# Main_Board.net
KiCad netlist of a schematic drawn in Altium Designer
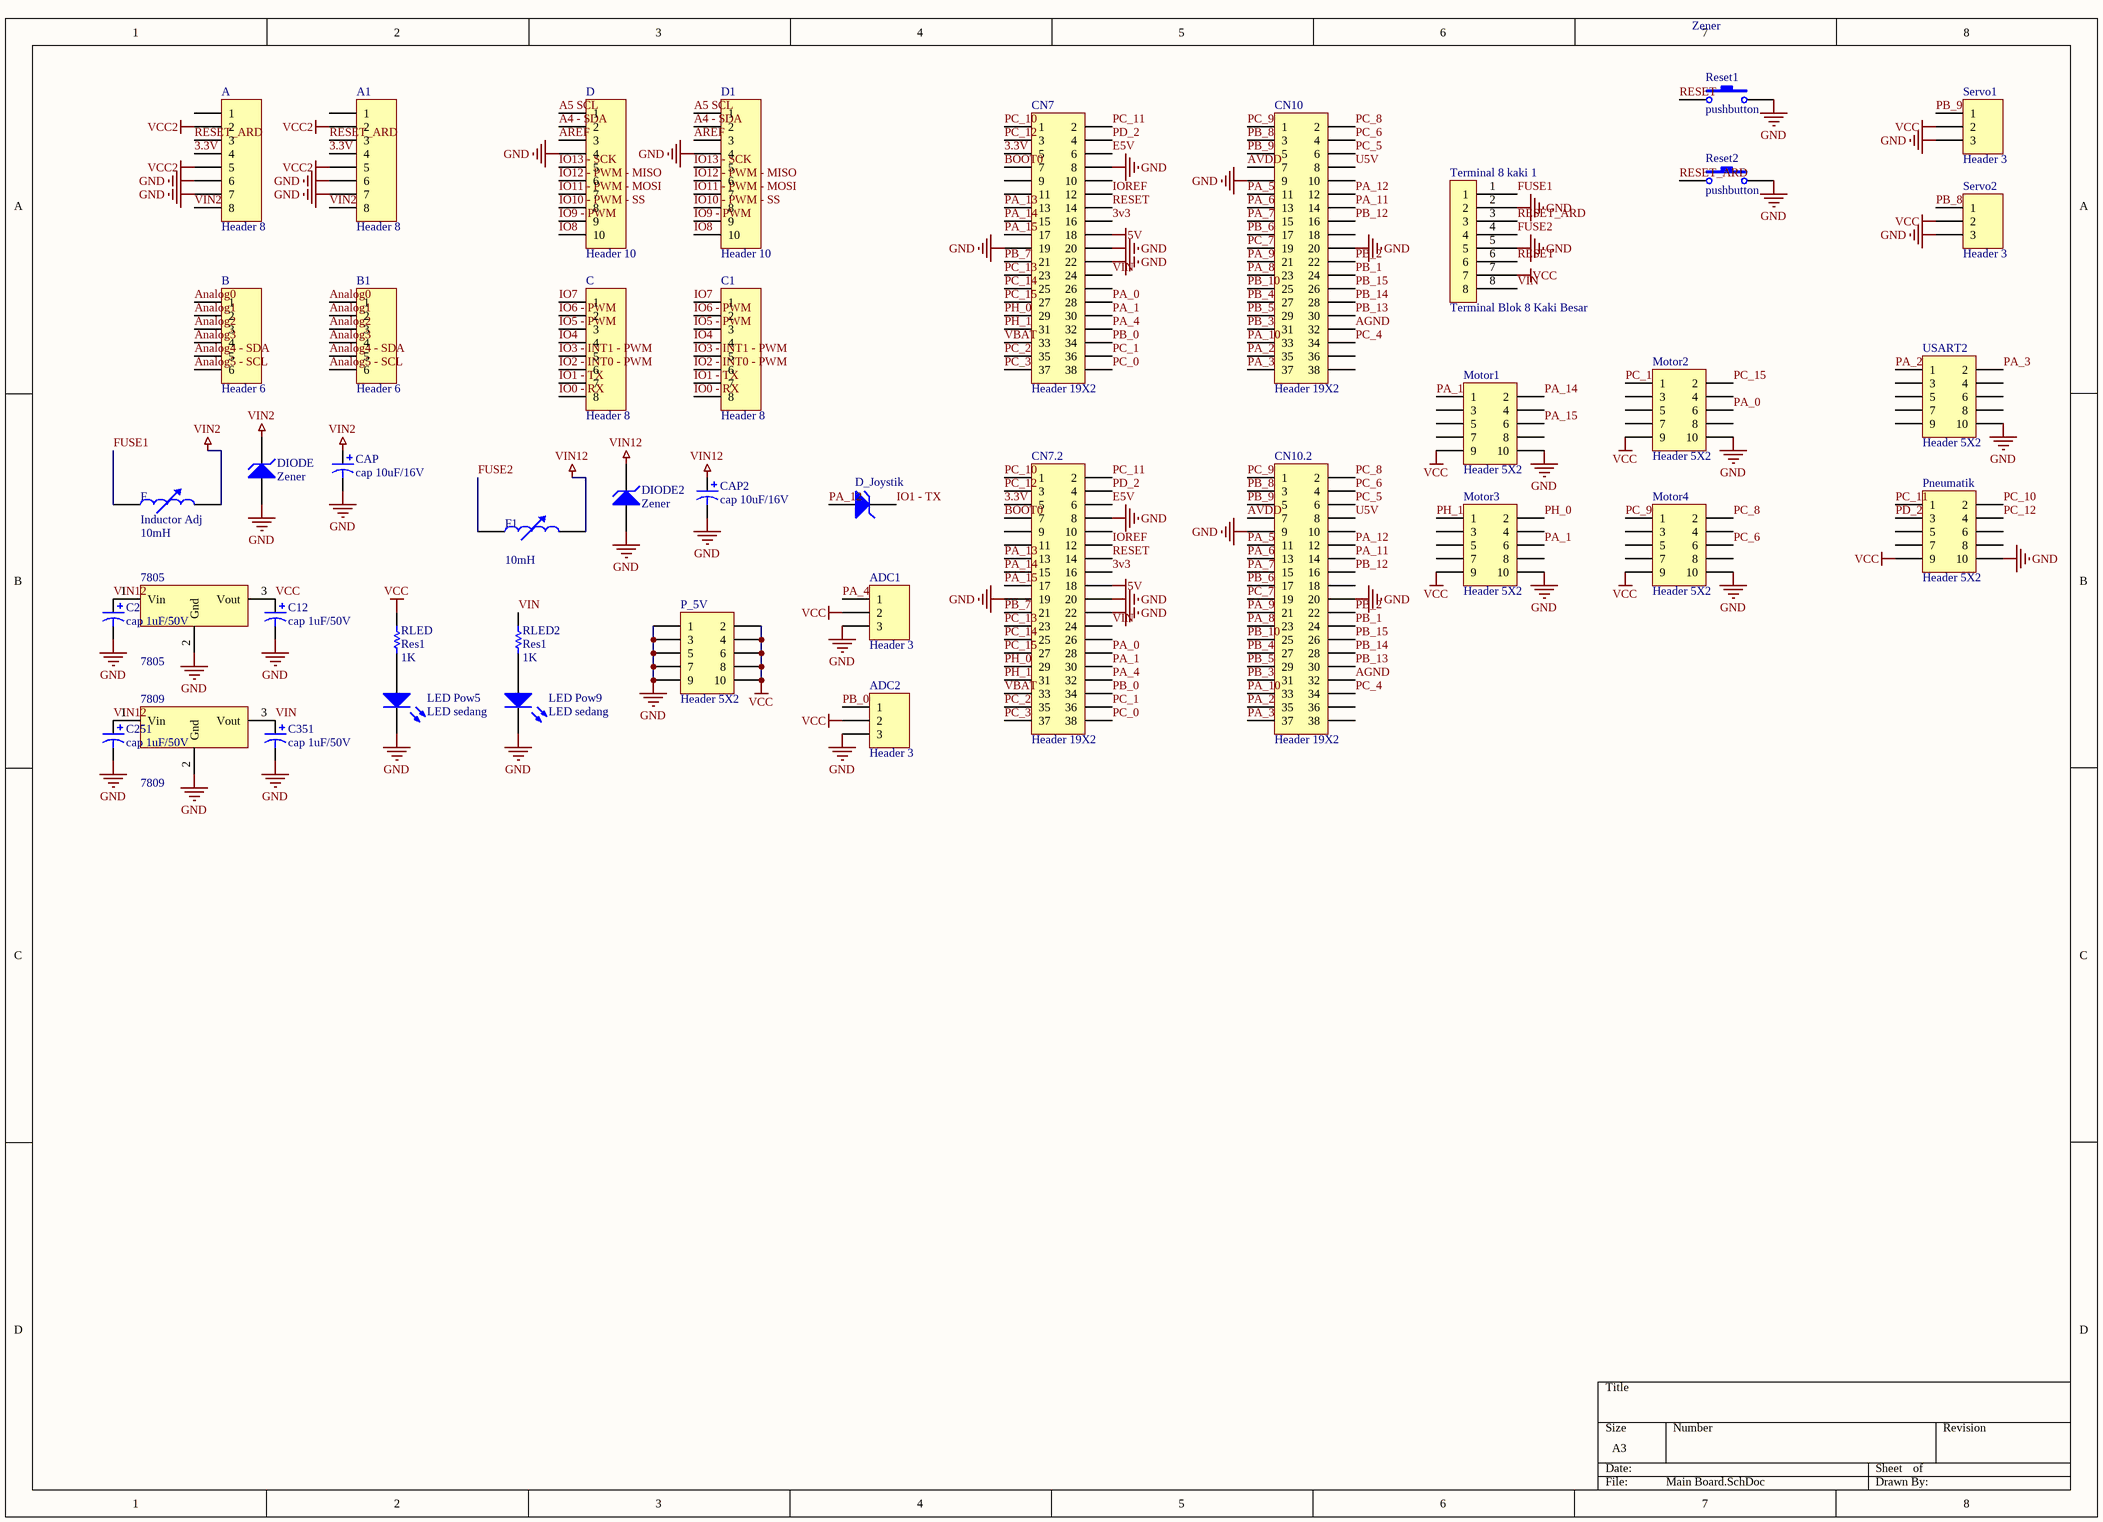
[diagram p0: Main Board.SchDoc]

(export (version "E")
  (design (tool "Eeschema 10.0.6"))
  (components
    (comp (ref "7805")
      (value "7805")
      (footprint "78XX/79XX")
      (libsource (lib "agfa other components") (part "7805/7809/7812/7905/7909/7912"))
    )
    (comp (ref "7809")
      (value "7809")
      (footprint "78XX/79XX")
      (libsource (lib "agfa other components") (part "7805/7809/7812/7905/7909/7912"))
    )
    (comp (ref "A")
      (value "Header 8")
      (footprint "HDR1X8")
      (description "Header, 8-Pin")
      (fields (field (name "PUBLISHER") "Altium Limited"))
      (libsource (lib "Miscellaneous Connectors") (part "Header 8"))
    )
    (comp (ref "A1")
      (value "Header 8")
      (footprint "HDR1X8")
      (description "Header, 8-Pin")
      (fields (field (name "PUBLISHER") "Altium Limited"))
      (libsource (lib "Miscellaneous Connectors") (part "Header 8"))
    )
    (comp (ref "ADC1")
      (value "Header 3")
      (footprint "HDR1X3")
      (description "Header, 3-Pin")
      (fields (field (name "PUBLISHER") "Altium Limited"))
      (libsource (lib "Miscellaneous Connectors") (part "Header 3"))
    )
    (comp (ref "ADC2")
      (value "Header 3")
      (footprint "HDR1X3")
      (description "Header, 3-Pin")
      (fields (field (name "PUBLISHER") "Altium Limited"))
      (libsource (lib "Miscellaneous Connectors") (part "Header 3"))
    )
    (comp (ref "B")
      (value "Header 6")
      (footprint "HDR1X6")
      (description "Header, 6-Pin")
      (fields (field (name "PUBLISHER") "Altium Limited"))
      (libsource (lib "Miscellaneous Connectors") (part "Header 6"))
    )
    (comp (ref "B1")
      (value "Header 6")
      (footprint "HDR1X6")
      (description "Header, 6-Pin")
      (fields (field (name "PUBLISHER") "Altium Limited"))
      (libsource (lib "Miscellaneous Connectors") (part "Header 6"))
    )
    (comp (ref "C")
      (value "Header 8")
      (footprint "HDR1X8")
      (description "Header, 8-Pin")
      (fields (field (name "PUBLISHER") "Altium Limited"))
      (libsource (lib "Miscellaneous Connectors") (part "Header 8"))
    )
    (comp (ref "C1")
      (value "Header 8")
      (footprint "HDR1X8")
      (description "Header, 8-Pin")
      (fields (field (name "PUBLISHER") "Altium Limited"))
      (libsource (lib "Miscellaneous Connectors") (part "Header 8"))
    )
    (comp (ref "C2")
      (value "cap 1uF/50V")
      (footprint "cap 1uF/50V")
      (libsource (lib "agfa other components") (part "cap 1uF/50V"))
    )
    (comp (ref "C12")
      (value "cap 1uF/50V")
      (footprint "cap 1uF/50V")
      (libsource (lib "agfa other components") (part "cap 1uF/50V"))
    )
    (comp (ref "C251")
      (value "cap 1uF/50V")
      (footprint "cap 1uF/50V")
      (libsource (lib "agfa other components") (part "cap 1uF/50V"))
    )
    (comp (ref "C351")
      (value "cap 1uF/50V")
      (footprint "cap 1uF/50V")
      (libsource (lib "agfa other components") (part "cap 1uF/50V"))
    )
    (comp (ref "CAP")
      (value "cap 10uF/16V")
      (footprint "cap 10uF/16V")
      (libsource (lib "agfa other components") (part "cap 10uF/16V"))
    )
    (comp (ref "CAP2")
      (value "cap 10uF/16V")
      (footprint "cap 10uF/16V")
      (libsource (lib "agfa other components") (part "cap 10uF/16V"))
    )
    (comp (ref "CN7")
      (value "Header 19X2")
      (footprint "HDR2X19")
      (description "Header, 19-Pin, Dual row")
      (fields (field (name "PUBLISHER") "Altium Limited"))
      (libsource (lib "Miscellaneous Connectors") (part "Header 19X2"))
    )
    (comp (ref "CN7.2")
      (value "Header 19X2")
      (footprint "HDR2X19")
      (description "Header, 19-Pin, Dual row")
      (fields (field (name "PUBLISHER") "Altium Limited"))
      (libsource (lib "Miscellaneous Connectors") (part "Header 19X2"))
    )
    (comp (ref "CN10")
      (value "Header 19X2")
      (footprint "HDR2X19")
      (description "Header, 19-Pin, Dual row")
      (fields (field (name "PUBLISHER") "Altium Limited"))
      (libsource (lib "Miscellaneous Connectors") (part "Header 19X2"))
    )
    (comp (ref "CN10.2")
      (value "Header 19X2")
      (footprint "HDR2X19")
      (description "Header, 19-Pin, Dual row")
      (fields (field (name "PUBLISHER") "Altium Limited"))
      (libsource (lib "Miscellaneous Connectors") (part "Header 19X2"))
    )
    (comp (ref "D")
      (value "Header 10")
      (footprint "HDR1X10")
      (description "Header, 10-Pin")
      (fields (field (name "PUBLISHER") "Altium Limited"))
      (libsource (lib "Miscellaneous Connectors") (part "Header 10"))
    )
    (comp (ref "D1")
      (value "Header 10")
      (footprint "HDR1X10")
      (description "Header, 10-Pin")
      (fields (field (name "PUBLISHER") "Altium Limited"))
      (libsource (lib "Miscellaneous Connectors") (part "Header 10"))
    )
    (comp (ref "DIODE")
      (value "Zener")
      (footprint "D Zener")
      (libsource (lib "agfa other components") (part "D Zener"))
    )
    (comp (ref "DIODE2")
      (value "Zener")
      (footprint "D Zener")
      (libsource (lib "agfa other components") (part "D Zener"))
    )
    (comp (ref "D_Joystik")
      (value "Zener")
      (footprint "D Zener")
      (libsource (lib "agfa other components") (part "D Zener"))
    )
    (comp (ref "F")
      (value "Inductor Adj")
      (footprint "AXIAL-0.8")
      (description "Adjustable Inductor")
      (fields (field (name "ALTIUM_VALUE") "10mH") (field (name "PUBLISHER") "Altium Limited"))
      (libsource (lib "Miscellaneous Devices") (part "Inductor Adj"))
    )
    (comp (ref "F1")
      (value "10mH")
      (footprint "AXIAL-0.8")
      (description "Adjustable Inductor")
      (fields (field (name "Comment") "Inductor Adj") (field (name "PUBLISHER") "Altium Limited"))
      (libsource (lib "Miscellaneous Devices") (part "Inductor Adj"))
    )
    (comp (ref "LED Pow5")
      (value "LED sedang")
      (footprint "LED sedang")
      (libsource (lib "agfa other components") (part "LED sedang"))
    )
    (comp (ref "LED Pow9")
      (value "LED sedang")
      (footprint "LED sedang")
      (libsource (lib "agfa other components") (part "LED sedang"))
    )
    (comp (ref "Motor1")
      (value "Header 5X2")
      (footprint "HDR2X5")
      (description "Header, 5-Pin, Dual row")
      (fields (field (name "PUBLISHER") "Altium Limited"))
      (libsource (lib "Miscellaneous Connectors") (part "Header 5X2"))
    )
    (comp (ref "Motor2")
      (value "Header 5X2")
      (footprint "HDR2X5")
      (description "Header, 5-Pin, Dual row")
      (fields (field (name "PUBLISHER") "Altium Limited"))
      (libsource (lib "Miscellaneous Connectors") (part "Header 5X2"))
    )
    (comp (ref "Motor3")
      (value "Header 5X2")
      (footprint "HDR2X5")
      (description "Header, 5-Pin, Dual row")
      (fields (field (name "PUBLISHER") "Altium Limited"))
      (libsource (lib "Miscellaneous Connectors") (part "Header 5X2"))
    )
    (comp (ref "Motor4")
      (value "Header 5X2")
      (footprint "HDR2X5")
      (description "Header, 5-Pin, Dual row")
      (fields (field (name "PUBLISHER") "Altium Limited"))
      (libsource (lib "Miscellaneous Connectors") (part "Header 5X2"))
    )
    (comp (ref "Pneumatik")
      (value "Header 5X2")
      (footprint "HDR2X5")
      (description "Header, 5-Pin, Dual row")
      (fields (field (name "PUBLISHER") "Altium Limited"))
      (libsource (lib "Miscellaneous Connectors") (part "Header 5X2"))
    )
    (comp (ref "P_5V")
      (value "Header 5X2")
      (footprint "HDR2X5")
      (description "Header, 5-Pin, Dual row")
      (fields (field (name "PUBLISHER") "Altium Limited"))
      (libsource (lib "Miscellaneous Connectors") (part "Header 5X2"))
    )
    (comp (ref "Reset1")
      (value "pushbutton")
      (footprint "pushbutton")
      (libsource (lib "agfa other components") (part "pushbutton"))
    )
    (comp (ref "Reset2")
      (value "pushbutton")
      (footprint "pushbutton")
      (libsource (lib "agfa other components") (part "pushbutton"))
    )
    (comp (ref "RLED")
      (value "Res1")
      (footprint "AXIAL-0.3")
      (description "Resistor")
      (fields (field (name "ALTIUM_VALUE") "1K") (field (name "PUBLISHER") "Altium Limited"))
      (libsource (lib "Miscellaneous Devices") (part "Res1"))
    )
    (comp (ref "RLED2")
      (value "Res1")
      (footprint "AXIAL-0.3")
      (description "Resistor")
      (fields (field (name "ALTIUM_VALUE") "1K") (field (name "PUBLISHER") "Altium Limited"))
      (libsource (lib "Miscellaneous Devices") (part "Res1"))
    )
    (comp (ref "Servo1")
      (value "Header 3")
      (footprint "HDR1X3")
      (description "Header, 3-Pin")
      (fields (field (name "PUBLISHER") "Altium Limited"))
      (libsource (lib "Miscellaneous Connectors") (part "Header 3"))
    )
    (comp (ref "Servo2")
      (value "Header 3")
      (footprint "HDR1X3")
      (description "Header, 3-Pin")
      (fields (field (name "PUBLISHER") "Altium Limited"))
      (libsource (lib "Miscellaneous Connectors") (part "Header 3"))
    )
    (comp (ref "Terminal 8 kaki 1")
      (value "Terminal Blok 8 Kaki Besar")
      (footprint "TERMINAL 8 KAKI")
      (libsource (lib "Library Ausiher") (part "Terminal Block 8 kaki"))
    )
    (comp (ref "USART2")
      (value "Header 5X2")
      (footprint "HDR2X5")
      (description "Header, 5-Pin, Dual row")
      (fields (field (name "PUBLISHER") "Altium Limited"))
      (libsource (lib "Miscellaneous Connectors") (part "Header 5X2"))
    )
  )
  (nets
    (net (code "1") (name "/3.3V") (class "Default")
      (node (ref "A") (pin "4") (pinfunction "4_4") (pintype "passive"))
      (node (ref "A1") (pin "4") (pinfunction "4_4") (pintype "passive"))
      (node (ref "CN7") (pin "5") (pinfunction "5_5") (pintype "passive"))
      (node (ref "CN7.2") (pin "5") (pinfunction "5_5") (pintype "passive"))
    )
    (net (code "2") (name "/3v3") (class "Default")
      (node (ref "CN7") (pin "16") (pinfunction "16_16") (pintype "passive"))
      (node (ref "CN7.2") (pin "16") (pinfunction "16_16") (pintype "passive"))
    )
    (net (code "3") (name "/A4 - SDA") (class "Default")
      (node (ref "D") (pin "2") (pinfunction "2_2") (pintype "passive"))
      (node (ref "D1") (pin "2") (pinfunction "2_2") (pintype "passive"))
    )
    (net (code "4") (name "/A5 SCL") (class "Default")
      (node (ref "D") (pin "1") (pinfunction "1_1") (pintype "passive"))
      (node (ref "D1") (pin "1") (pinfunction "1_1") (pintype "passive"))
    )
    (net (code "5") (name "/AGND") (class "Default")
      (node (ref "CN10") (pin "32") (pinfunction "32_32") (pintype "passive"))
      (node (ref "CN10.2") (pin "32") (pinfunction "32_32") (pintype "passive"))
    )
    (net (code "6") (name "/AREF") (class "Default")
      (node (ref "D") (pin "3") (pinfunction "3_3") (pintype "passive"))
      (node (ref "D1") (pin "3") (pinfunction "3_3") (pintype "passive"))
    )
    (net (code "7") (name "/AVDD") (class "Default")
      (node (ref "CN10") (pin "7") (pinfunction "7_7") (pintype "passive"))
      (node (ref "CN10.2") (pin "7") (pinfunction "7_7") (pintype "passive"))
    )
    (net (code "8") (name "/Analog0") (class "Default")
      (node (ref "B") (pin "1") (pinfunction "1_1") (pintype "passive"))
      (node (ref "B1") (pin "1") (pinfunction "1_1") (pintype "passive"))
    )
    (net (code "9") (name "/Analog1") (class "Default")
      (node (ref "B") (pin "2") (pinfunction "2_2") (pintype "passive"))
      (node (ref "B1") (pin "2") (pinfunction "2_2") (pintype "passive"))
    )
    (net (code "10") (name "/Analog2") (class "Default")
      (node (ref "B") (pin "3") (pinfunction "3_3") (pintype "passive"))
      (node (ref "B1") (pin "3") (pinfunction "3_3") (pintype "passive"))
    )
    (net (code "11") (name "/Analog3") (class "Default")
      (node (ref "B") (pin "4") (pinfunction "4_4") (pintype "passive"))
      (node (ref "B1") (pin "4") (pinfunction "4_4") (pintype "passive"))
    )
    (net (code "12") (name "/Analog4 - SDA") (class "Default")
      (node (ref "B") (pin "5") (pinfunction "5_5") (pintype "passive"))
      (node (ref "B1") (pin "5") (pinfunction "5_5") (pintype "passive"))
    )
    (net (code "13") (name "/Analog5 - SCL") (class "Default")
      (node (ref "B") (pin "6") (pinfunction "6_6") (pintype "passive"))
      (node (ref "B1") (pin "6") (pinfunction "6_6") (pintype "passive"))
    )
    (net (code "14") (name "/BOOT0") (class "Default")
      (node (ref "CN7") (pin "7") (pinfunction "7_7") (pintype "passive"))
      (node (ref "CN7.2") (pin "7") (pinfunction "7_7") (pintype "passive"))
    )
    (net (code "15") (name "/E5V") (class "Default")
      (node (ref "CN7") (pin "6") (pinfunction "6_6") (pintype "passive"))
      (node (ref "CN7.2") (pin "6") (pinfunction "6_6") (pintype "passive"))
    )
    (net (code "16") (name "/FUSE1") (class "Default")
      (node (ref "F") (pin "1") (pinfunction "1_1") (pintype "passive"))
      (node (ref "Terminal 8 kaki 1") (pin "1") (pinfunction "1_1") (pintype "passive"))
    )
    (net (code "17") (name "/FUSE2") (class "Default")
      (node (ref "F1") (pin "1") (pinfunction "1_1") (pintype "passive"))
      (node (ref "Terminal 8 kaki 1") (pin "4") (pinfunction "4_4") (pintype "passive"))
    )
    (net (code "18") (name "/IO0 - RX") (class "Default")
      (node (ref "C") (pin "8") (pinfunction "8_8") (pintype "passive"))
      (node (ref "C1") (pin "8") (pinfunction "8_8") (pintype "passive"))
    )
    (net (code "19") (name "/IO1 - TX") (class "Default")
      (node (ref "C") (pin "7") (pinfunction "7_7") (pintype "passive"))
      (node (ref "C1") (pin "7") (pinfunction "7_7") (pintype "passive"))
      (node (ref "D_Joystik") (pin "2") (pinfunction "K_2") (pintype "passive"))
    )
    (net (code "20") (name "/IO2 - INT0 - PWM") (class "Default")
      (node (ref "C") (pin "6") (pinfunction "6_6") (pintype "passive"))
      (node (ref "C1") (pin "6") (pinfunction "6_6") (pintype "passive"))
    )
    (net (code "21") (name "/IO3 - INT1 - PWM") (class "Default")
      (node (ref "C") (pin "5") (pinfunction "5_5") (pintype "passive"))
      (node (ref "C1") (pin "5") (pinfunction "5_5") (pintype "passive"))
    )
    (net (code "22") (name "/IO4") (class "Default")
      (node (ref "C") (pin "4") (pinfunction "4_4") (pintype "passive"))
      (node (ref "C1") (pin "4") (pinfunction "4_4") (pintype "passive"))
    )
    (net (code "23") (name "/IO5 - PWM") (class "Default")
      (node (ref "C") (pin "3") (pinfunction "3_3") (pintype "passive"))
      (node (ref "C1") (pin "3") (pinfunction "3_3") (pintype "passive"))
    )
    (net (code "24") (name "/IO6 - PWM") (class "Default")
      (node (ref "C") (pin "2") (pinfunction "2_2") (pintype "passive"))
      (node (ref "C1") (pin "2") (pinfunction "2_2") (pintype "passive"))
    )
    (net (code "25") (name "/IO7") (class "Default")
      (node (ref "C") (pin "1") (pinfunction "1_1") (pintype "passive"))
      (node (ref "C1") (pin "1") (pinfunction "1_1") (pintype "passive"))
    )
    (net (code "26") (name "/IO8") (class "Default")
      (node (ref "D") (pin "10") (pinfunction "10_10") (pintype "passive"))
      (node (ref "D1") (pin "10") (pinfunction "10_10") (pintype "passive"))
    )
    (net (code "27") (name "/IO9 - PWM") (class "Default")
      (node (ref "D") (pin "9") (pinfunction "9_9") (pintype "passive"))
      (node (ref "D1") (pin "9") (pinfunction "9_9") (pintype "passive"))
    )
    (net (code "28") (name "/IO10 - PWM - SS") (class "Default")
      (node (ref "D") (pin "8") (pinfunction "8_8") (pintype "passive"))
      (node (ref "D1") (pin "8") (pinfunction "8_8") (pintype "passive"))
    )
    (net (code "29") (name "/IO11 - PWM - MOSI") (class "Default")
      (node (ref "D") (pin "7") (pinfunction "7_7") (pintype "passive"))
      (node (ref "D1") (pin "7") (pinfunction "7_7") (pintype "passive"))
    )
    (net (code "30") (name "/IO12 - PWM - MISO") (class "Default")
      (node (ref "D") (pin "6") (pinfunction "6_6") (pintype "passive"))
      (node (ref "D1") (pin "6") (pinfunction "6_6") (pintype "passive"))
    )
    (net (code "31") (name "/IO13 - SCK") (class "Default")
      (node (ref "D") (pin "5") (pinfunction "5_5") (pintype "passive"))
      (node (ref "D1") (pin "5") (pinfunction "5_5") (pintype "passive"))
    )
    (net (code "32") (name "/IOREF") (class "Default")
      (node (ref "CN7") (pin "12") (pinfunction "12_12") (pintype "passive"))
      (node (ref "CN7.2") (pin "12") (pinfunction "12_12") (pintype "passive"))
    )
    (net (code "33") (name "/PA_0") (class "Default")
      (node (ref "CN7") (pin "28") (pinfunction "28_28") (pintype "passive"))
      (node (ref "CN7.2") (pin "28") (pinfunction "28_28") (pintype "passive"))
      (node (ref "Motor2") (pin "6") (pinfunction "6_6") (pintype "passive"))
    )
    (net (code "34") (name "/PA_1") (class "Default")
      (node (ref "CN7") (pin "30") (pinfunction "30_30") (pintype "passive"))
      (node (ref "CN7.2") (pin "30") (pinfunction "30_30") (pintype "passive"))
      (node (ref "Motor3") (pin "6") (pinfunction "6_6") (pintype "passive"))
    )
    (net (code "35") (name "/PA_2") (class "Default")
      (node (ref "CN10") (pin "35") (pinfunction "35_35") (pintype "passive"))
      (node (ref "CN10.2") (pin "35") (pinfunction "35_35") (pintype "passive"))
      (node (ref "USART2") (pin "1") (pinfunction "1_1") (pintype "passive"))
    )
    (net (code "36") (name "/PA_3") (class "Default")
      (node (ref "CN10") (pin "37") (pinfunction "37_37") (pintype "passive"))
      (node (ref "CN10.2") (pin "37") (pinfunction "37_37") (pintype "passive"))
      (node (ref "USART2") (pin "2") (pinfunction "2_2") (pintype "passive"))
    )
    (net (code "37") (name "/PA_4") (class "Default")
      (node (ref "ADC1") (pin "1") (pinfunction "1_1") (pintype "passive"))
      (node (ref "CN7") (pin "32") (pinfunction "32_32") (pintype "passive"))
      (node (ref "CN7.2") (pin "32") (pinfunction "32_32") (pintype "passive"))
    )
    (net (code "38") (name "/PA_5") (class "Default")
      (node (ref "CN10") (pin "11") (pinfunction "11_11") (pintype "passive"))
      (node (ref "CN10.2") (pin "11") (pinfunction "11_11") (pintype "passive"))
    )
    (net (code "39") (name "/PA_6") (class "Default")
      (node (ref "CN10") (pin "13") (pinfunction "13_13") (pintype "passive"))
      (node (ref "CN10.2") (pin "13") (pinfunction "13_13") (pintype "passive"))
    )
    (net (code "40") (name "/PA_7") (class "Default")
      (node (ref "CN10") (pin "15") (pinfunction "15_15") (pintype "passive"))
      (node (ref "CN10.2") (pin "15") (pinfunction "15_15") (pintype "passive"))
    )
    (net (code "41") (name "/PA_8") (class "Default")
      (node (ref "CN10") (pin "23") (pinfunction "23_23") (pintype "passive"))
      (node (ref "CN10.2") (pin "23") (pinfunction "23_23") (pintype "passive"))
    )
    (net (code "42") (name "/PA_9") (class "Default")
      (node (ref "CN10") (pin "21") (pinfunction "21_21") (pintype "passive"))
      (node (ref "CN10.2") (pin "21") (pinfunction "21_21") (pintype "passive"))
    )
    (net (code "43") (name "/PA_10") (class "Default")
      (node (ref "CN10") (pin "33") (pinfunction "33_33") (pintype "passive"))
      (node (ref "CN10.2") (pin "33") (pinfunction "33_33") (pintype "passive"))
    )
    (net (code "44") (name "/PA_11") (class "Default")
      (node (ref "CN10") (pin "14") (pinfunction "14_14") (pintype "passive"))
      (node (ref "CN10.2") (pin "14") (pinfunction "14_14") (pintype "passive"))
    )
    (net (code "45") (name "/PA_12") (class "Default")
      (node (ref "CN10") (pin "12") (pinfunction "12_12") (pintype "passive"))
      (node (ref "CN10.2") (pin "12") (pinfunction "12_12") (pintype "passive"))
      (node (ref "D_Joystik") (pin "1") (pinfunction "A_1") (pintype "passive"))
    )
    (net (code "46") (name "/PA_13") (class "Default")
      (node (ref "CN7") (pin "13") (pinfunction "13_13") (pintype "passive"))
      (node (ref "CN7.2") (pin "13") (pinfunction "13_13") (pintype "passive"))
      (node (ref "Motor1") (pin "1") (pinfunction "1_1") (pintype "passive"))
    )
    (net (code "47") (name "/PA_14") (class "Default")
      (node (ref "CN7") (pin "15") (pinfunction "15_15") (pintype "passive"))
      (node (ref "CN7.2") (pin "15") (pinfunction "15_15") (pintype "passive"))
      (node (ref "Motor1") (pin "2") (pinfunction "2_2") (pintype "passive"))
    )
    (net (code "48") (name "/PA_15") (class "Default")
      (node (ref "CN7") (pin "17") (pinfunction "17_17") (pintype "passive"))
      (node (ref "CN7.2") (pin "17") (pinfunction "17_17") (pintype "passive"))
      (node (ref "Motor1") (pin "6") (pinfunction "6_6") (pintype "passive"))
    )
    (net (code "49") (name "/PB_0") (class "Default")
      (node (ref "ADC2") (pin "1") (pinfunction "1_1") (pintype "passive"))
      (node (ref "CN7") (pin "34") (pinfunction "34_34") (pintype "passive"))
      (node (ref "CN7.2") (pin "34") (pinfunction "34_34") (pintype "passive"))
    )
    (net (code "50") (name "/PB_1") (class "Default")
      (node (ref "CN10") (pin "24") (pinfunction "24_24") (pintype "passive"))
      (node (ref "CN10.2") (pin "24") (pinfunction "24_24") (pintype "passive"))
    )
    (net (code "51") (name "/PB_2") (class "Default")
      (node (ref "CN10") (pin "22") (pinfunction "22_22") (pintype "passive"))
      (node (ref "CN10.2") (pin "22") (pinfunction "22_22") (pintype "passive"))
    )
    (net (code "52") (name "/PB_3") (class "Default")
      (node (ref "CN10") (pin "31") (pinfunction "31_31") (pintype "passive"))
      (node (ref "CN10.2") (pin "31") (pinfunction "31_31") (pintype "passive"))
    )
    (net (code "53") (name "/PB_4") (class "Default")
      (node (ref "CN10") (pin "27") (pinfunction "27_27") (pintype "passive"))
      (node (ref "CN10.2") (pin "27") (pinfunction "27_27") (pintype "passive"))
    )
    (net (code "54") (name "/PB_5") (class "Default")
      (node (ref "CN10") (pin "29") (pinfunction "29_29") (pintype "passive"))
      (node (ref "CN10.2") (pin "29") (pinfunction "29_29") (pintype "passive"))
    )
    (net (code "55") (name "/PB_6") (class "Default")
      (node (ref "CN10") (pin "17") (pinfunction "17_17") (pintype "passive"))
      (node (ref "CN10.2") (pin "17") (pinfunction "17_17") (pintype "passive"))
    )
    (net (code "56") (name "/PB_7") (class "Default")
      (node (ref "CN7") (pin "21") (pinfunction "21_21") (pintype "passive"))
      (node (ref "CN7.2") (pin "21") (pinfunction "21_21") (pintype "passive"))
    )
    (net (code "57") (name "/PB_8") (class "Default")
      (node (ref "CN10") (pin "3") (pinfunction "3_3") (pintype "passive"))
      (node (ref "CN10.2") (pin "3") (pinfunction "3_3") (pintype "passive"))
      (node (ref "Servo2") (pin "1") (pinfunction "1_1") (pintype "passive"))
    )
    (net (code "58") (name "/PB_9") (class "Default")
      (node (ref "CN10") (pin "5") (pinfunction "5_5") (pintype "passive"))
      (node (ref "CN10.2") (pin "5") (pinfunction "5_5") (pintype "passive"))
      (node (ref "Servo1") (pin "1") (pinfunction "1_1") (pintype "passive"))
    )
    (net (code "59") (name "/PB_10") (class "Default")
      (node (ref "CN10") (pin "25") (pinfunction "25_25") (pintype "passive"))
      (node (ref "CN10.2") (pin "25") (pinfunction "25_25") (pintype "passive"))
    )
    (net (code "60") (name "/PB_12") (class "Default")
      (node (ref "CN10") (pin "16") (pinfunction "16_16") (pintype "passive"))
      (node (ref "CN10.2") (pin "16") (pinfunction "16_16") (pintype "passive"))
    )
    (net (code "61") (name "/PB_13") (class "Default")
      (node (ref "CN10") (pin "30") (pinfunction "30_30") (pintype "passive"))
      (node (ref "CN10.2") (pin "30") (pinfunction "30_30") (pintype "passive"))
    )
    (net (code "62") (name "/PB_14") (class "Default")
      (node (ref "CN10") (pin "28") (pinfunction "28_28") (pintype "passive"))
      (node (ref "CN10.2") (pin "28") (pinfunction "28_28") (pintype "passive"))
    )
    (net (code "63") (name "/PB_15") (class "Default")
      (node (ref "CN10") (pin "26") (pinfunction "26_26") (pintype "passive"))
      (node (ref "CN10.2") (pin "26") (pinfunction "26_26") (pintype "passive"))
    )
    (net (code "64") (name "/PC_0") (class "Default")
      (node (ref "CN7") (pin "38") (pinfunction "38_38") (pintype "passive"))
      (node (ref "CN7.2") (pin "38") (pinfunction "38_38") (pintype "passive"))
    )
    (net (code "65") (name "/PC_1") (class "Default")
      (node (ref "CN7") (pin "36") (pinfunction "36_36") (pintype "passive"))
      (node (ref "CN7.2") (pin "36") (pinfunction "36_36") (pintype "passive"))
    )
    (net (code "66") (name "/PC_2") (class "Default")
      (node (ref "CN7") (pin "35") (pinfunction "35_35") (pintype "passive"))
      (node (ref "CN7.2") (pin "35") (pinfunction "35_35") (pintype "passive"))
    )
    (net (code "67") (name "/PC_3") (class "Default")
      (node (ref "CN7") (pin "37") (pinfunction "37_37") (pintype "passive"))
      (node (ref "CN7.2") (pin "37") (pinfunction "37_37") (pintype "passive"))
    )
    (net (code "68") (name "/PC_4") (class "Default")
      (node (ref "CN10") (pin "34") (pinfunction "34_34") (pintype "passive"))
      (node (ref "CN10.2") (pin "34") (pinfunction "34_34") (pintype "passive"))
    )
    (net (code "69") (name "/PC_5") (class "Default")
      (node (ref "CN10") (pin "6") (pinfunction "6_6") (pintype "passive"))
      (node (ref "CN10.2") (pin "6") (pinfunction "6_6") (pintype "passive"))
    )
    (net (code "70") (name "/PC_6") (class "Default")
      (node (ref "CN10") (pin "4") (pinfunction "4_4") (pintype "passive"))
      (node (ref "CN10.2") (pin "4") (pinfunction "4_4") (pintype "passive"))
      (node (ref "Motor4") (pin "6") (pinfunction "6_6") (pintype "passive"))
    )
    (net (code "71") (name "/PC_7") (class "Default")
      (node (ref "CN10") (pin "19") (pinfunction "19_19") (pintype "passive"))
      (node (ref "CN10.2") (pin "19") (pinfunction "19_19") (pintype "passive"))
    )
    (net (code "72") (name "/PC_8") (class "Default")
      (node (ref "CN10") (pin "2") (pinfunction "2_2") (pintype "passive"))
      (node (ref "CN10.2") (pin "2") (pinfunction "2_2") (pintype "passive"))
      (node (ref "Motor4") (pin "2") (pinfunction "2_2") (pintype "passive"))
    )
    (net (code "73") (name "/PC_9") (class "Default")
      (node (ref "CN10") (pin "1") (pinfunction "1_1") (pintype "passive"))
      (node (ref "CN10.2") (pin "1") (pinfunction "1_1") (pintype "passive"))
      (node (ref "Motor4") (pin "1") (pinfunction "1_1") (pintype "passive"))
    )
    (net (code "74") (name "/PC_10") (class "Default")
      (node (ref "CN7") (pin "1") (pinfunction "1_1") (pintype "passive"))
      (node (ref "CN7.2") (pin "1") (pinfunction "1_1") (pintype "passive"))
      (node (ref "Pneumatik") (pin "2") (pinfunction "2_2") (pintype "passive"))
    )
    (net (code "75") (name "/PC_11") (class "Default")
      (node (ref "CN7") (pin "2") (pinfunction "2_2") (pintype "passive"))
      (node (ref "CN7.2") (pin "2") (pinfunction "2_2") (pintype "passive"))
      (node (ref "Pneumatik") (pin "1") (pinfunction "1_1") (pintype "passive"))
    )
    (net (code "76") (name "/PC_12") (class "Default")
      (node (ref "CN7") (pin "3") (pinfunction "3_3") (pintype "passive"))
      (node (ref "CN7.2") (pin "3") (pinfunction "3_3") (pintype "passive"))
      (node (ref "Pneumatik") (pin "4") (pinfunction "4_4") (pintype "passive"))
    )
    (net (code "77") (name "/PC_13") (class "Default")
      (node (ref "CN7") (pin "23") (pinfunction "23_23") (pintype "passive"))
      (node (ref "CN7.2") (pin "23") (pinfunction "23_23") (pintype "passive"))
    )
    (net (code "78") (name "/PC_14") (class "Default")
      (node (ref "CN7") (pin "25") (pinfunction "25_25") (pintype "passive"))
      (node (ref "CN7.2") (pin "25") (pinfunction "25_25") (pintype "passive"))
      (node (ref "Motor2") (pin "1") (pinfunction "1_1") (pintype "passive"))
    )
    (net (code "79") (name "/PC_15") (class "Default")
      (node (ref "CN7") (pin "27") (pinfunction "27_27") (pintype "passive"))
      (node (ref "CN7.2") (pin "27") (pinfunction "27_27") (pintype "passive"))
      (node (ref "Motor2") (pin "2") (pinfunction "2_2") (pintype "passive"))
    )
    (net (code "80") (name "/PD_2") (class "Default")
      (node (ref "CN7") (pin "4") (pinfunction "4_4") (pintype "passive"))
      (node (ref "CN7.2") (pin "4") (pinfunction "4_4") (pintype "passive"))
      (node (ref "Pneumatik") (pin "3") (pinfunction "3_3") (pintype "passive"))
    )
    (net (code "81") (name "/PH_0") (class "Default")
      (node (ref "CN7") (pin "29") (pinfunction "29_29") (pintype "passive"))
      (node (ref "CN7.2") (pin "29") (pinfunction "29_29") (pintype "passive"))
      (node (ref "Motor3") (pin "2") (pinfunction "2_2") (pintype "passive"))
    )
    (net (code "82") (name "/PH_1") (class "Default")
      (node (ref "CN7") (pin "31") (pinfunction "31_31") (pintype "passive"))
      (node (ref "CN7.2") (pin "31") (pinfunction "31_31") (pintype "passive"))
      (node (ref "Motor3") (pin "1") (pinfunction "1_1") (pintype "passive"))
    )
    (net (code "83") (name "/RESET") (class "Default")
      (node (ref "CN7") (pin "14") (pinfunction "14_14") (pintype "passive"))
      (node (ref "CN7.2") (pin "14") (pinfunction "14_14") (pintype "passive"))
      (node (ref "Reset1") (pin "1") (pinfunction "1_1") (pintype "passive"))
      (node (ref "Terminal 8 kaki 1") (pin "6") (pinfunction "6_6") (pintype "passive"))
    )
    (net (code "84") (name "/RESET_ARD") (class "Default")
      (node (ref "A") (pin "3") (pinfunction "3_3") (pintype "passive"))
      (node (ref "A1") (pin "3") (pinfunction "3_3") (pintype "passive"))
      (node (ref "Reset2") (pin "1") (pinfunction "1_1") (pintype "passive"))
      (node (ref "Terminal 8 kaki 1") (pin "3") (pinfunction "3_3") (pintype "passive"))
    )
    (net (code "85") (name "/U5V") (class "Default")
      (node (ref "CN10") (pin "8") (pinfunction "8_8") (pintype "passive"))
      (node (ref "CN10.2") (pin "8") (pinfunction "8_8") (pintype "passive"))
    )
    (net (code "86") (name "/VBAT") (class "Default")
      (node (ref "CN7") (pin "33") (pinfunction "33_33") (pintype "passive"))
      (node (ref "CN7.2") (pin "33") (pinfunction "33_33") (pintype "passive"))
    )
    (net (code "87") (name "/VIN") (class "Default")
      (node (ref "7809") (pin "3") (pinfunction "Vout_3") (pintype "passive"))
      (node (ref "C351") (pin "1") (pinfunction "1_1") (pintype "passive"))
      (node (ref "CN7") (pin "24") (pinfunction "24_24") (pintype "passive"))
      (node (ref "CN7.2") (pin "24") (pinfunction "24_24") (pintype "passive"))
      (node (ref "RLED2") (pin "2") (pinfunction "2_2") (pintype "passive"))
      (node (ref "Terminal 8 kaki 1") (pin "8") (pinfunction "8_8") (pintype "passive"))
    )
    (net (code "88") (name "5V") (class "Default")
      (node (ref "CN7") (pin "18") (pinfunction "18_18") (pintype "passive"))
      (node (ref "CN7.2") (pin "18") (pinfunction "18_18") (pintype "passive"))
    )
    (net (code "89") (name "GND") (class "Default")
      (node (ref "7805") (pin "2") (pinfunction "Gnd_2") (pintype "passive"))
      (node (ref "7809") (pin "2") (pinfunction "Gnd_2") (pintype "passive"))
      (node (ref "A") (pin "6") (pinfunction "6_6") (pintype "passive"))
      (node (ref "A") (pin "7") (pinfunction "7_7") (pintype "passive"))
      (node (ref "A1") (pin "6") (pinfunction "6_6") (pintype "passive"))
      (node (ref "A1") (pin "7") (pinfunction "7_7") (pintype "passive"))
      (node (ref "ADC1") (pin "3") (pinfunction "3_3") (pintype "passive"))
      (node (ref "ADC2") (pin "3") (pinfunction "3_3") (pintype "passive"))
      (node (ref "C12") (pin "2") (pinfunction "2_2") (pintype "passive"))
      (node (ref "C2") (pin "2") (pinfunction "2_2") (pintype "passive"))
      (node (ref "C251") (pin "2") (pinfunction "2_2") (pintype "passive"))
      (node (ref "C351") (pin "2") (pinfunction "2_2") (pintype "passive"))
      (node (ref "CAP") (pin "2") (pinfunction "2_2") (pintype "passive"))
      (node (ref "CAP2") (pin "2") (pinfunction "2_2") (pintype "passive"))
      (node (ref "CN10") (pin "20") (pinfunction "20_20") (pintype "passive"))
      (node (ref "CN10") (pin "9") (pinfunction "9_9") (pintype "passive"))
      (node (ref "CN10.2") (pin "20") (pinfunction "20_20") (pintype "passive"))
      (node (ref "CN10.2") (pin "9") (pinfunction "9_9") (pintype "passive"))
      (node (ref "CN7") (pin "19") (pinfunction "19_19") (pintype "passive"))
      (node (ref "CN7") (pin "20") (pinfunction "20_20") (pintype "passive"))
      (node (ref "CN7") (pin "22") (pinfunction "22_22") (pintype "passive"))
      (node (ref "CN7") (pin "8") (pinfunction "8_8") (pintype "passive"))
      (node (ref "CN7.2") (pin "19") (pinfunction "19_19") (pintype "passive"))
      (node (ref "CN7.2") (pin "20") (pinfunction "20_20") (pintype "passive"))
      (node (ref "CN7.2") (pin "22") (pinfunction "22_22") (pintype "passive"))
      (node (ref "CN7.2") (pin "8") (pinfunction "8_8") (pintype "passive"))
      (node (ref "D") (pin "4") (pinfunction "4_4") (pintype "passive"))
      (node (ref "D1") (pin "4") (pinfunction "4_4") (pintype "passive"))
      (node (ref "DIODE") (pin "1") (pinfunction "A_1") (pintype "passive"))
      (node (ref "DIODE2") (pin "1") (pinfunction "A_1") (pintype "passive"))
      (node (ref "LED Pow5") (pin "2") (pinfunction "K_2") (pintype "passive"))
      (node (ref "LED Pow9") (pin "2") (pinfunction "K_2") (pintype "passive"))
      (node (ref "Motor1") (pin "10") (pinfunction "10_10") (pintype "passive"))
      (node (ref "Motor2") (pin "10") (pinfunction "10_10") (pintype "passive"))
      (node (ref "Motor3") (pin "10") (pinfunction "10_10") (pintype "passive"))
      (node (ref "Motor4") (pin "10") (pinfunction "10_10") (pintype "passive"))
      (node (ref "P_5V") (pin "1") (pinfunction "1_1") (pintype "passive"))
      (node (ref "P_5V") (pin "3") (pinfunction "3_3") (pintype "passive"))
      (node (ref "P_5V") (pin "5") (pinfunction "5_5") (pintype "passive"))
      (node (ref "P_5V") (pin "7") (pinfunction "7_7") (pintype "passive"))
      (node (ref "P_5V") (pin "9") (pinfunction "9_9") (pintype "passive"))
      (node (ref "Pneumatik") (pin "10") (pinfunction "10_10") (pintype "passive"))
      (node (ref "Reset1") (pin "2") (pinfunction "2_2") (pintype "passive"))
      (node (ref "Reset2") (pin "2") (pinfunction "2_2") (pintype "passive"))
      (node (ref "Servo1") (pin "3") (pinfunction "3_3") (pintype "passive"))
      (node (ref "Servo2") (pin "3") (pinfunction "3_3") (pintype "passive"))
      (node (ref "Terminal 8 kaki 1") (pin "2") (pinfunction "2_2") (pintype "passive"))
      (node (ref "Terminal 8 kaki 1") (pin "5") (pinfunction "5_5") (pintype "passive"))
      (node (ref "USART2") (pin "10") (pinfunction "10_10") (pintype "passive"))
    )
    (net (code "90") (name "Net-(LED Pow5-A)") (class "Default")
      (node (ref "LED Pow5") (pin "1") (pinfunction "A_1") (pintype "passive"))
      (node (ref "RLED") (pin "1") (pinfunction "1_1") (pintype "passive"))
    )
    (net (code "91") (name "Net-(LED Pow9-A)") (class "Default")
      (node (ref "LED Pow9") (pin "1") (pinfunction "A_1") (pintype "passive"))
      (node (ref "RLED2") (pin "1") (pinfunction "1_1") (pintype "passive"))
    )
    (net (code "92") (name "VCC") (class "Default")
      (node (ref "7805") (pin "3") (pinfunction "Vout_3") (pintype "passive"))
      (node (ref "ADC1") (pin "2") (pinfunction "2_2") (pintype "passive"))
      (node (ref "ADC2") (pin "2") (pinfunction "2_2") (pintype "passive"))
      (node (ref "C12") (pin "1") (pinfunction "1_1") (pintype "passive"))
      (node (ref "Motor1") (pin "9") (pinfunction "9_9") (pintype "passive"))
      (node (ref "Motor2") (pin "9") (pinfunction "9_9") (pintype "passive"))
      (node (ref "Motor3") (pin "9") (pinfunction "9_9") (pintype "passive"))
      (node (ref "Motor4") (pin "9") (pinfunction "9_9") (pintype "passive"))
      (node (ref "P_5V") (pin "10") (pinfunction "10_10") (pintype "passive"))
      (node (ref "P_5V") (pin "2") (pinfunction "2_2") (pintype "passive"))
      (node (ref "P_5V") (pin "4") (pinfunction "4_4") (pintype "passive"))
      (node (ref "P_5V") (pin "6") (pinfunction "6_6") (pintype "passive"))
      (node (ref "P_5V") (pin "8") (pinfunction "8_8") (pintype "passive"))
      (node (ref "Pneumatik") (pin "9") (pinfunction "9_9") (pintype "passive"))
      (node (ref "RLED") (pin "2") (pinfunction "2_2") (pintype "passive"))
      (node (ref "Servo1") (pin "2") (pinfunction "2_2") (pintype "passive"))
      (node (ref "Servo2") (pin "2") (pinfunction "2_2") (pintype "passive"))
      (node (ref "Terminal 8 kaki 1") (pin "7") (pinfunction "7_7") (pintype "passive"))
    )
    (net (code "93") (name "VCC2") (class "Default")
      (node (ref "A") (pin "2") (pinfunction "2_2") (pintype "passive"))
      (node (ref "A") (pin "5") (pinfunction "5_5") (pintype "passive"))
      (node (ref "A1") (pin "2") (pinfunction "2_2") (pintype "passive"))
      (node (ref "A1") (pin "5") (pinfunction "5_5") (pintype "passive"))
    )
    (net (code "94") (name "VIN2") (class "Default")
      (node (ref "A") (pin "8") (pinfunction "8_8") (pintype "passive"))
      (node (ref "A1") (pin "8") (pinfunction "8_8") (pintype "passive"))
      (node (ref "CAP") (pin "1") (pinfunction "1_1") (pintype "passive"))
      (node (ref "DIODE") (pin "2") (pinfunction "K_2") (pintype "passive"))
      (node (ref "F") (pin "2") (pinfunction "2_2") (pintype "passive"))
    )
    (net (code "95") (name "VIN12") (class "Default")
      (node (ref "7805") (pin "1") (pinfunction "Vin_1") (pintype "passive"))
      (node (ref "7809") (pin "1") (pinfunction "Vin_1") (pintype "passive"))
      (node (ref "C2") (pin "1") (pinfunction "1_1") (pintype "passive"))
      (node (ref "C251") (pin "1") (pinfunction "1_1") (pintype "passive"))
      (node (ref "CAP2") (pin "1") (pinfunction "1_1") (pintype "passive"))
      (node (ref "DIODE2") (pin "2") (pinfunction "K_2") (pintype "passive"))
      (node (ref "F1") (pin "2") (pinfunction "2_2") (pintype "passive"))
    )
    (net (code "96") (name "unconnected-(A-Pad1)") (class "Default")
      (node (ref "A") (pin "1") (pinfunction "1_1") (pintype "passive"))
    )
    (net (code "97") (name "unconnected-(A1-Pad1)") (class "Default")
      (node (ref "A1") (pin "1") (pinfunction "1_1") (pintype "passive"))
    )
    (net (code "98") (name "unconnected-(CN7-Pad9)") (class "Default")
      (node (ref "CN7") (pin "9") (pinfunction "9_9") (pintype "passive"))
    )
    (net (code "99") (name "unconnected-(CN7-Pad10)") (class "Default")
      (node (ref "CN7") (pin "10") (pinfunction "10_10") (pintype "passive"))
    )
    (net (code "100") (name "unconnected-(CN7-Pad11)") (class "Default")
      (node (ref "CN7") (pin "11") (pinfunction "11_11") (pintype "passive"))
    )
    (net (code "101") (name "unconnected-(CN7-Pad26)") (class "Default")
      (node (ref "CN7") (pin "26") (pinfunction "26_26") (pintype "passive"))
    )
    (net (code "102") (name "unconnected-(CN7.2-Pad9)") (class "Default")
      (node (ref "CN7.2") (pin "9") (pinfunction "9_9") (pintype "passive"))
    )
    (net (code "103") (name "unconnected-(CN7.2-Pad10)") (class "Default")
      (node (ref "CN7.2") (pin "10") (pinfunction "10_10") (pintype "passive"))
    )
    (net (code "104") (name "unconnected-(CN7.2-Pad11)") (class "Default")
      (node (ref "CN7.2") (pin "11") (pinfunction "11_11") (pintype "passive"))
    )
    (net (code "105") (name "unconnected-(CN7.2-Pad26)") (class "Default")
      (node (ref "CN7.2") (pin "26") (pinfunction "26_26") (pintype "passive"))
    )
    (net (code "106") (name "unconnected-(CN10-Pad10)") (class "Default")
      (node (ref "CN10") (pin "10") (pinfunction "10_10") (pintype "passive"))
    )
    (net (code "107") (name "unconnected-(CN10-Pad18)") (class "Default")
      (node (ref "CN10") (pin "18") (pinfunction "18_18") (pintype "passive"))
    )
    (net (code "108") (name "unconnected-(CN10-Pad36)") (class "Default")
      (node (ref "CN10") (pin "36") (pinfunction "36_36") (pintype "passive"))
    )
    (net (code "109") (name "unconnected-(CN10-Pad38)") (class "Default")
      (node (ref "CN10") (pin "38") (pinfunction "38_38") (pintype "passive"))
    )
    (net (code "110") (name "unconnected-(CN10.2-Pad10)") (class "Default")
      (node (ref "CN10.2") (pin "10") (pinfunction "10_10") (pintype "passive"))
    )
    (net (code "111") (name "unconnected-(CN10.2-Pad18)") (class "Default")
      (node (ref "CN10.2") (pin "18") (pinfunction "18_18") (pintype "passive"))
    )
    (net (code "112") (name "unconnected-(CN10.2-Pad36)") (class "Default")
      (node (ref "CN10.2") (pin "36") (pinfunction "36_36") (pintype "passive"))
    )
    (net (code "113") (name "unconnected-(CN10.2-Pad38)") (class "Default")
      (node (ref "CN10.2") (pin "38") (pinfunction "38_38") (pintype "passive"))
    )
    (net (code "114") (name "unconnected-(Motor1-Pad3)") (class "Default")
      (node (ref "Motor1") (pin "3") (pinfunction "3_3") (pintype "passive"))
    )
    (net (code "115") (name "unconnected-(Motor1-Pad4)") (class "Default")
      (node (ref "Motor1") (pin "4") (pinfunction "4_4") (pintype "passive"))
    )
    (net (code "116") (name "unconnected-(Motor1-Pad5)") (class "Default")
      (node (ref "Motor1") (pin "5") (pinfunction "5_5") (pintype "passive"))
    )
    (net (code "117") (name "unconnected-(Motor1-Pad7)") (class "Default")
      (node (ref "Motor1") (pin "7") (pinfunction "7_7") (pintype "passive"))
    )
    (net (code "118") (name "unconnected-(Motor1-Pad8)") (class "Default")
      (node (ref "Motor1") (pin "8") (pinfunction "8_8") (pintype "passive"))
    )
    (net (code "119") (name "unconnected-(Motor2-Pad3)") (class "Default")
      (node (ref "Motor2") (pin "3") (pinfunction "3_3") (pintype "passive"))
    )
    (net (code "120") (name "unconnected-(Motor2-Pad4)") (class "Default")
      (node (ref "Motor2") (pin "4") (pinfunction "4_4") (pintype "passive"))
    )
    (net (code "121") (name "unconnected-(Motor2-Pad5)") (class "Default")
      (node (ref "Motor2") (pin "5") (pinfunction "5_5") (pintype "passive"))
    )
    (net (code "122") (name "unconnected-(Motor2-Pad7)") (class "Default")
      (node (ref "Motor2") (pin "7") (pinfunction "7_7") (pintype "passive"))
    )
    (net (code "123") (name "unconnected-(Motor2-Pad8)") (class "Default")
      (node (ref "Motor2") (pin "8") (pinfunction "8_8") (pintype "passive"))
    )
    (net (code "124") (name "unconnected-(Motor3-Pad3)") (class "Default")
      (node (ref "Motor3") (pin "3") (pinfunction "3_3") (pintype "passive"))
    )
    (net (code "125") (name "unconnected-(Motor3-Pad4)") (class "Default")
      (node (ref "Motor3") (pin "4") (pinfunction "4_4") (pintype "passive"))
    )
    (net (code "126") (name "unconnected-(Motor3-Pad5)") (class "Default")
      (node (ref "Motor3") (pin "5") (pinfunction "5_5") (pintype "passive"))
    )
    (net (code "127") (name "unconnected-(Motor3-Pad7)") (class "Default")
      (node (ref "Motor3") (pin "7") (pinfunction "7_7") (pintype "passive"))
    )
    (net (code "128") (name "unconnected-(Motor3-Pad8)") (class "Default")
      (node (ref "Motor3") (pin "8") (pinfunction "8_8") (pintype "passive"))
    )
    (net (code "129") (name "unconnected-(Motor4-Pad3)") (class "Default")
      (node (ref "Motor4") (pin "3") (pinfunction "3_3") (pintype "passive"))
    )
    (net (code "130") (name "unconnected-(Motor4-Pad4)") (class "Default")
      (node (ref "Motor4") (pin "4") (pinfunction "4_4") (pintype "passive"))
    )
    (net (code "131") (name "unconnected-(Motor4-Pad5)") (class "Default")
      (node (ref "Motor4") (pin "5") (pinfunction "5_5") (pintype "passive"))
    )
    (net (code "132") (name "unconnected-(Motor4-Pad7)") (class "Default")
      (node (ref "Motor4") (pin "7") (pinfunction "7_7") (pintype "passive"))
    )
    (net (code "133") (name "unconnected-(Motor4-Pad8)") (class "Default")
      (node (ref "Motor4") (pin "8") (pinfunction "8_8") (pintype "passive"))
    )
    (net (code "134") (name "unconnected-(Pneumatik-Pad5)") (class "Default")
      (node (ref "Pneumatik") (pin "5") (pinfunction "5_5") (pintype "passive"))
    )
    (net (code "135") (name "unconnected-(Pneumatik-Pad6)") (class "Default")
      (node (ref "Pneumatik") (pin "6") (pinfunction "6_6") (pintype "passive"))
    )
    (net (code "136") (name "unconnected-(Pneumatik-Pad7)") (class "Default")
      (node (ref "Pneumatik") (pin "7") (pinfunction "7_7") (pintype "passive"))
    )
    (net (code "137") (name "unconnected-(Pneumatik-Pad8)") (class "Default")
      (node (ref "Pneumatik") (pin "8") (pinfunction "8_8") (pintype "passive"))
    )
    (net (code "138") (name "unconnected-(USART2-Pad3)") (class "Default")
      (node (ref "USART2") (pin "3") (pinfunction "3_3") (pintype "passive"))
    )
    (net (code "139") (name "unconnected-(USART2-Pad4)") (class "Default")
      (node (ref "USART2") (pin "4") (pinfunction "4_4") (pintype "passive"))
    )
    (net (code "140") (name "unconnected-(USART2-Pad5)") (class "Default")
      (node (ref "USART2") (pin "5") (pinfunction "5_5") (pintype "passive"))
    )
    (net (code "141") (name "unconnected-(USART2-Pad6)") (class "Default")
      (node (ref "USART2") (pin "6") (pinfunction "6_6") (pintype "passive"))
    )
    (net (code "142") (name "unconnected-(USART2-Pad7)") (class "Default")
      (node (ref "USART2") (pin "7") (pinfunction "7_7") (pintype "passive"))
    )
    (net (code "143") (name "unconnected-(USART2-Pad8)") (class "Default")
      (node (ref "USART2") (pin "8") (pinfunction "8_8") (pintype "passive"))
    )
    (net (code "144") (name "unconnected-(USART2-Pad9)") (class "Default")
      (node (ref "USART2") (pin "9") (pinfunction "9_9") (pintype "passive"))
    )
  )
)
